# uwbsender.net
KiCad netlist of a schematic drawn in EAGLE
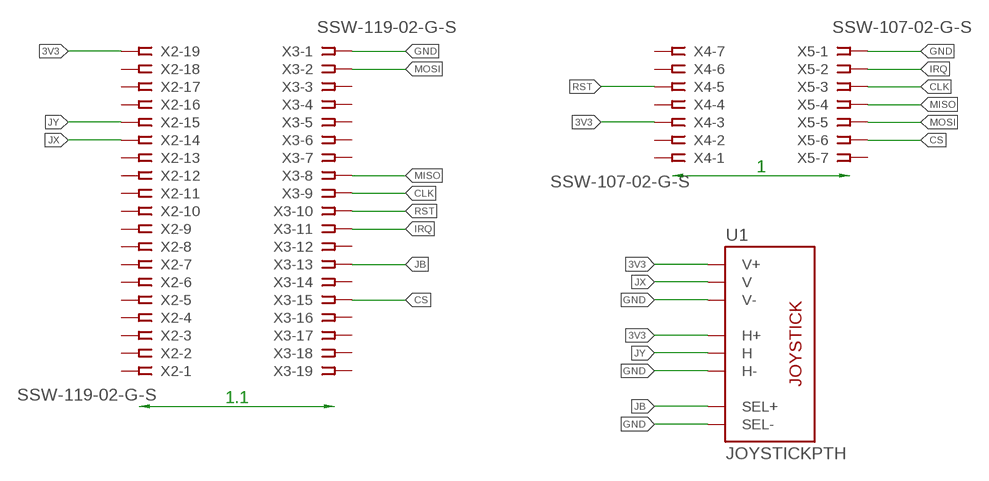
[diagram p0: schematic, sheet 1]

(export (version "E")
  (design (tool "Eeschema 10.0.6"))
  (components
    (comp (ref "U1")
      (value "JOYSTICKPTH")
      (footprint "eagle-import:JOYSTICK")
      (libsource (lib "eagle-import") (part "JOYSTICKPTH"))
    )
    (comp (ref "X2")
      (value "SSW-119-02-G-S")
      (footprint "eagle-import:SSW-119-02-G-S")
      (fields (field (name "MF") "Samtec Inc."))
      (libsource (lib "eagle-import") (part "SSW-119-02-G-S"))
    )
    (comp (ref "X3")
      (value "SSW-119-02-G-S")
      (footprint "eagle-import:SSW-119-02-G-S")
      (fields (field (name "MF") "Samtec Inc."))
      (libsource (lib "eagle-import") (part "SSW-119-02-G-S"))
    )
    (comp (ref "X4")
      (value "SSW-107-02-G-S")
      (footprint "eagle-import:SSW-107-02-G-S")
      (fields (field (name "MF") "Samtec Inc."))
      (libsource (lib "eagle-import") (part "SSW-107-02-G-S"))
    )
    (comp (ref "X5")
      (value "SSW-107-02-G-S")
      (footprint "eagle-import:SSW-107-02-G-S")
      (fields (field (name "MF") "Samtec Inc."))
      (libsource (lib "eagle-import") (part "SSW-107-02-G-S"))
    )
  )
  (nets
    (net (code "1") (name "3V3") (class "Default")
      (node (ref "U1") (pin "H1") (pinfunction "H+_H1") (pintype "bidirectional"))
      (node (ref "U1") (pin "V1") (pinfunction "V+_V1") (pintype "bidirectional"))
      (node (ref "X2") (pin "19") (pinfunction "1_19") (pintype "passive"))
      (node (ref "X4") (pin "3") (pinfunction "1_3") (pintype "passive"))
    )
    (net (code "2") (name "CLK") (class "Default")
      (node (ref "X3") (pin "9") (pinfunction "1_9") (pintype "passive"))
      (node (ref "X5") (pin "3") (pinfunction "1_3") (pintype "passive"))
    )
    (net (code "3") (name "CS") (class "Default")
      (node (ref "X3") (pin "15") (pinfunction "1_15") (pintype "passive"))
      (node (ref "X5") (pin "6") (pinfunction "1_6") (pintype "passive"))
    )
    (net (code "4") (name "GND") (class "Default")
      (node (ref "U1") (pin "B2A") (pinfunction "SEL-_B2A") (pintype "bidirectional"))
      (node (ref "U1") (pin "H3") (pinfunction "H-_H3") (pintype "bidirectional"))
      (node (ref "U1") (pin "V3") (pinfunction "V-_V3") (pintype "bidirectional"))
      (node (ref "X3") (pin "1") (pinfunction "1_1") (pintype "passive"))
      (node (ref "X5") (pin "1") (pinfunction "1_1") (pintype "passive"))
    )
    (net (code "5") (name "IRQ") (class "Default")
      (node (ref "X3") (pin "11") (pinfunction "1_11") (pintype "passive"))
      (node (ref "X5") (pin "2") (pinfunction "1_2") (pintype "passive"))
    )
    (net (code "6") (name "JB") (class "Default")
      (node (ref "U1") (pin "B1A") (pinfunction "SEL+_B1A") (pintype "bidirectional"))
      (node (ref "X3") (pin "13") (pinfunction "1_13") (pintype "passive"))
    )
    (net (code "7") (name "JX") (class "Default")
      (node (ref "U1") (pin "V2") (pinfunction "V_V2") (pintype "bidirectional"))
      (node (ref "X2") (pin "14") (pinfunction "1_14") (pintype "passive"))
    )
    (net (code "8") (name "JY") (class "Default")
      (node (ref "U1") (pin "H2") (pinfunction "H_H2") (pintype "bidirectional"))
      (node (ref "X2") (pin "15") (pinfunction "1_15") (pintype "passive"))
    )
    (net (code "9") (name "MISO") (class "Default")
      (node (ref "X3") (pin "8") (pinfunction "1_8") (pintype "passive"))
      (node (ref "X5") (pin "4") (pinfunction "1_4") (pintype "passive"))
    )
    (net (code "10") (name "MOSI") (class "Default")
      (node (ref "X3") (pin "2") (pinfunction "1_2") (pintype "passive"))
      (node (ref "X5") (pin "5") (pinfunction "1_5") (pintype "passive"))
    )
    (net (code "11") (name "RST") (class "Default")
      (node (ref "X3") (pin "10") (pinfunction "1_10") (pintype "passive"))
      (node (ref "X4") (pin "5") (pinfunction "1_5") (pintype "passive"))
    )
    (net (code "12") (name "unconnected-(X2-Pad1)") (class "Default")
      (node (ref "X2") (pin "1") (pinfunction "1_1") (pintype "passive"))
    )
    (net (code "13") (name "unconnected-(X2B-1-Pad10)") (class "Default")
      (node (ref "X2") (pin "10") (pinfunction "1_10") (pintype "passive"))
    )
    (net (code "14") (name "unconnected-(X2C-1-Pad11)") (class "Default")
      (node (ref "X2") (pin "11") (pinfunction "1_11") (pintype "passive"))
    )
    (net (code "15") (name "unconnected-(X2D-1-Pad12)") (class "Default")
      (node (ref "X2") (pin "12") (pinfunction "1_12") (pintype "passive"))
    )
    (net (code "16") (name "unconnected-(X2E-1-Pad13)") (class "Default")
      (node (ref "X2") (pin "13") (pinfunction "1_13") (pintype "passive"))
    )
    (net (code "17") (name "unconnected-(X2H-1-Pad16)") (class "Default")
      (node (ref "X2") (pin "16") (pinfunction "1_16") (pintype "passive"))
    )
    (net (code "18") (name "unconnected-(X2I-1-Pad17)") (class "Default")
      (node (ref "X2") (pin "17") (pinfunction "1_17") (pintype "passive"))
    )
    (net (code "19") (name "unconnected-(X2J-1-Pad18)") (class "Default")
      (node (ref "X2") (pin "18") (pinfunction "1_18") (pintype "passive"))
    )
    (net (code "20") (name "unconnected-(X2L-1-Pad2)") (class "Default")
      (node (ref "X2") (pin "2") (pinfunction "1_2") (pintype "passive"))
    )
    (net (code "21") (name "unconnected-(X2M-1-Pad3)") (class "Default")
      (node (ref "X2") (pin "3") (pinfunction "1_3") (pintype "passive"))
    )
    (net (code "22") (name "unconnected-(X2N-1-Pad4)") (class "Default")
      (node (ref "X2") (pin "4") (pinfunction "1_4") (pintype "passive"))
    )
    (net (code "23") (name "unconnected-(X2O-1-Pad5)") (class "Default")
      (node (ref "X2") (pin "5") (pinfunction "1_5") (pintype "passive"))
    )
    (net (code "24") (name "unconnected-(X2P-1-Pad6)") (class "Default")
      (node (ref "X2") (pin "6") (pinfunction "1_6") (pintype "passive"))
    )
    (net (code "25") (name "unconnected-(X2Q-1-Pad7)") (class "Default")
      (node (ref "X2") (pin "7") (pinfunction "1_7") (pintype "passive"))
    )
    (net (code "26") (name "unconnected-(X2R-1-Pad8)") (class "Default")
      (node (ref "X2") (pin "8") (pinfunction "1_8") (pintype "passive"))
    )
    (net (code "27") (name "unconnected-(X2S-1-Pad9)") (class "Default")
      (node (ref "X2") (pin "9") (pinfunction "1_9") (pintype "passive"))
    )
    (net (code "28") (name "unconnected-(X3D-1-Pad12)") (class "Default")
      (node (ref "X3") (pin "12") (pinfunction "1_12") (pintype "passive"))
    )
    (net (code "29") (name "unconnected-(X3F-1-Pad14)") (class "Default")
      (node (ref "X3") (pin "14") (pinfunction "1_14") (pintype "passive"))
    )
    (net (code "30") (name "unconnected-(X3H-1-Pad16)") (class "Default")
      (node (ref "X3") (pin "16") (pinfunction "1_16") (pintype "passive"))
    )
    (net (code "31") (name "unconnected-(X3I-1-Pad17)") (class "Default")
      (node (ref "X3") (pin "17") (pinfunction "1_17") (pintype "passive"))
    )
    (net (code "32") (name "unconnected-(X3J-1-Pad18)") (class "Default")
      (node (ref "X3") (pin "18") (pinfunction "1_18") (pintype "passive"))
    )
    (net (code "33") (name "unconnected-(X3K-1-Pad19)") (class "Default")
      (node (ref "X3") (pin "19") (pinfunction "1_19") (pintype "passive"))
    )
    (net (code "34") (name "unconnected-(X3M-1-Pad3)") (class "Default")
      (node (ref "X3") (pin "3") (pinfunction "1_3") (pintype "passive"))
    )
    (net (code "35") (name "unconnected-(X3N-1-Pad4)") (class "Default")
      (node (ref "X3") (pin "4") (pinfunction "1_4") (pintype "passive"))
    )
    (net (code "36") (name "unconnected-(X3O-1-Pad5)") (class "Default")
      (node (ref "X3") (pin "5") (pinfunction "1_5") (pintype "passive"))
    )
    (net (code "37") (name "unconnected-(X3P-1-Pad6)") (class "Default")
      (node (ref "X3") (pin "6") (pinfunction "1_6") (pintype "passive"))
    )
    (net (code "38") (name "unconnected-(X3Q-1-Pad7)") (class "Default")
      (node (ref "X3") (pin "7") (pinfunction "1_7") (pintype "passive"))
    )
    (net (code "39") (name "unconnected-(X4-Pad1)") (class "Default")
      (node (ref "X4") (pin "1") (pinfunction "1_1") (pintype "passive"))
    )
    (net (code "40") (name "unconnected-(X4B-1-Pad2)") (class "Default")
      (node (ref "X4") (pin "2") (pinfunction "1_2") (pintype "passive"))
    )
    (net (code "41") (name "unconnected-(X4D-1-Pad4)") (class "Default")
      (node (ref "X4") (pin "4") (pinfunction "1_4") (pintype "passive"))
    )
    (net (code "42") (name "unconnected-(X4F-1-Pad6)") (class "Default")
      (node (ref "X4") (pin "6") (pinfunction "1_6") (pintype "passive"))
    )
    (net (code "43") (name "unconnected-(X4G-1-Pad7)") (class "Default")
      (node (ref "X4") (pin "7") (pinfunction "1_7") (pintype "passive"))
    )
    (net (code "44") (name "unconnected-(X5G-1-Pad7)") (class "Default")
      (node (ref "X5") (pin "7") (pinfunction "1_7") (pintype "passive"))
    )
  )
)
